# LDO-3V3.net
KiCad netlist of a schematic drawn in Altium Designer
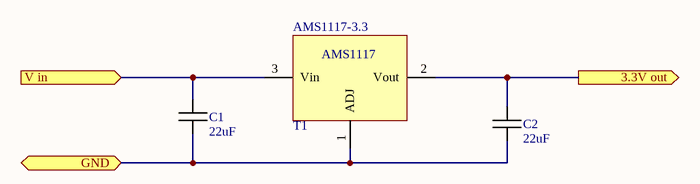
[diagram p0: LDO-3V3.SchDoc]

(export (version "E")
  (design (tool "Eeschema 10.0.6"))
  (components
    (comp (ref "AMS1117-3.3")
      (value "T1")
      (footprint "SOT-223-3")
      (libsource (lib "AMS1117 breakout") (part "AMS1117"))
    )
    (comp (ref "C1")
      (value "22uF")
      (footprint "C 0805 / 2012")
      (libsource (lib "AMS1117 breakout") (part "Capacitor"))
    )
    (comp (ref "C2")
      (value "22uF")
      (footprint "C 0805 / 2012")
      (libsource (lib "AMS1117 breakout") (part "Capacitor"))
    )
  )
  (nets
    (net (code "1") (name "/3.3V out") (class "Default")
      (node (ref "AMS1117-3.3") (pin "2") (pinfunction "Vout_2") (pintype "passive"))
      (node (ref "C2") (pin "2") (pinfunction "2_2") (pintype "passive"))
    )
    (net (code "2") (name "/GND") (class "Default")
      (node (ref "AMS1117-3.3") (pin "1") (pinfunction "ADJ_1") (pintype "passive"))
      (node (ref "C1") (pin "1") (pinfunction "1_1") (pintype "passive"))
      (node (ref "C2") (pin "1") (pinfunction "1_1") (pintype "passive"))
    )
    (net (code "3") (name "/V in") (class "Default")
      (node (ref "AMS1117-3.3") (pin "3") (pinfunction "Vin_3") (pintype "passive"))
      (node (ref "C1") (pin "2") (pinfunction "2_2") (pintype "passive"))
    )
  )
)
